# rf315i.net
KiCad netlist of a schematic drawn in EAGLE
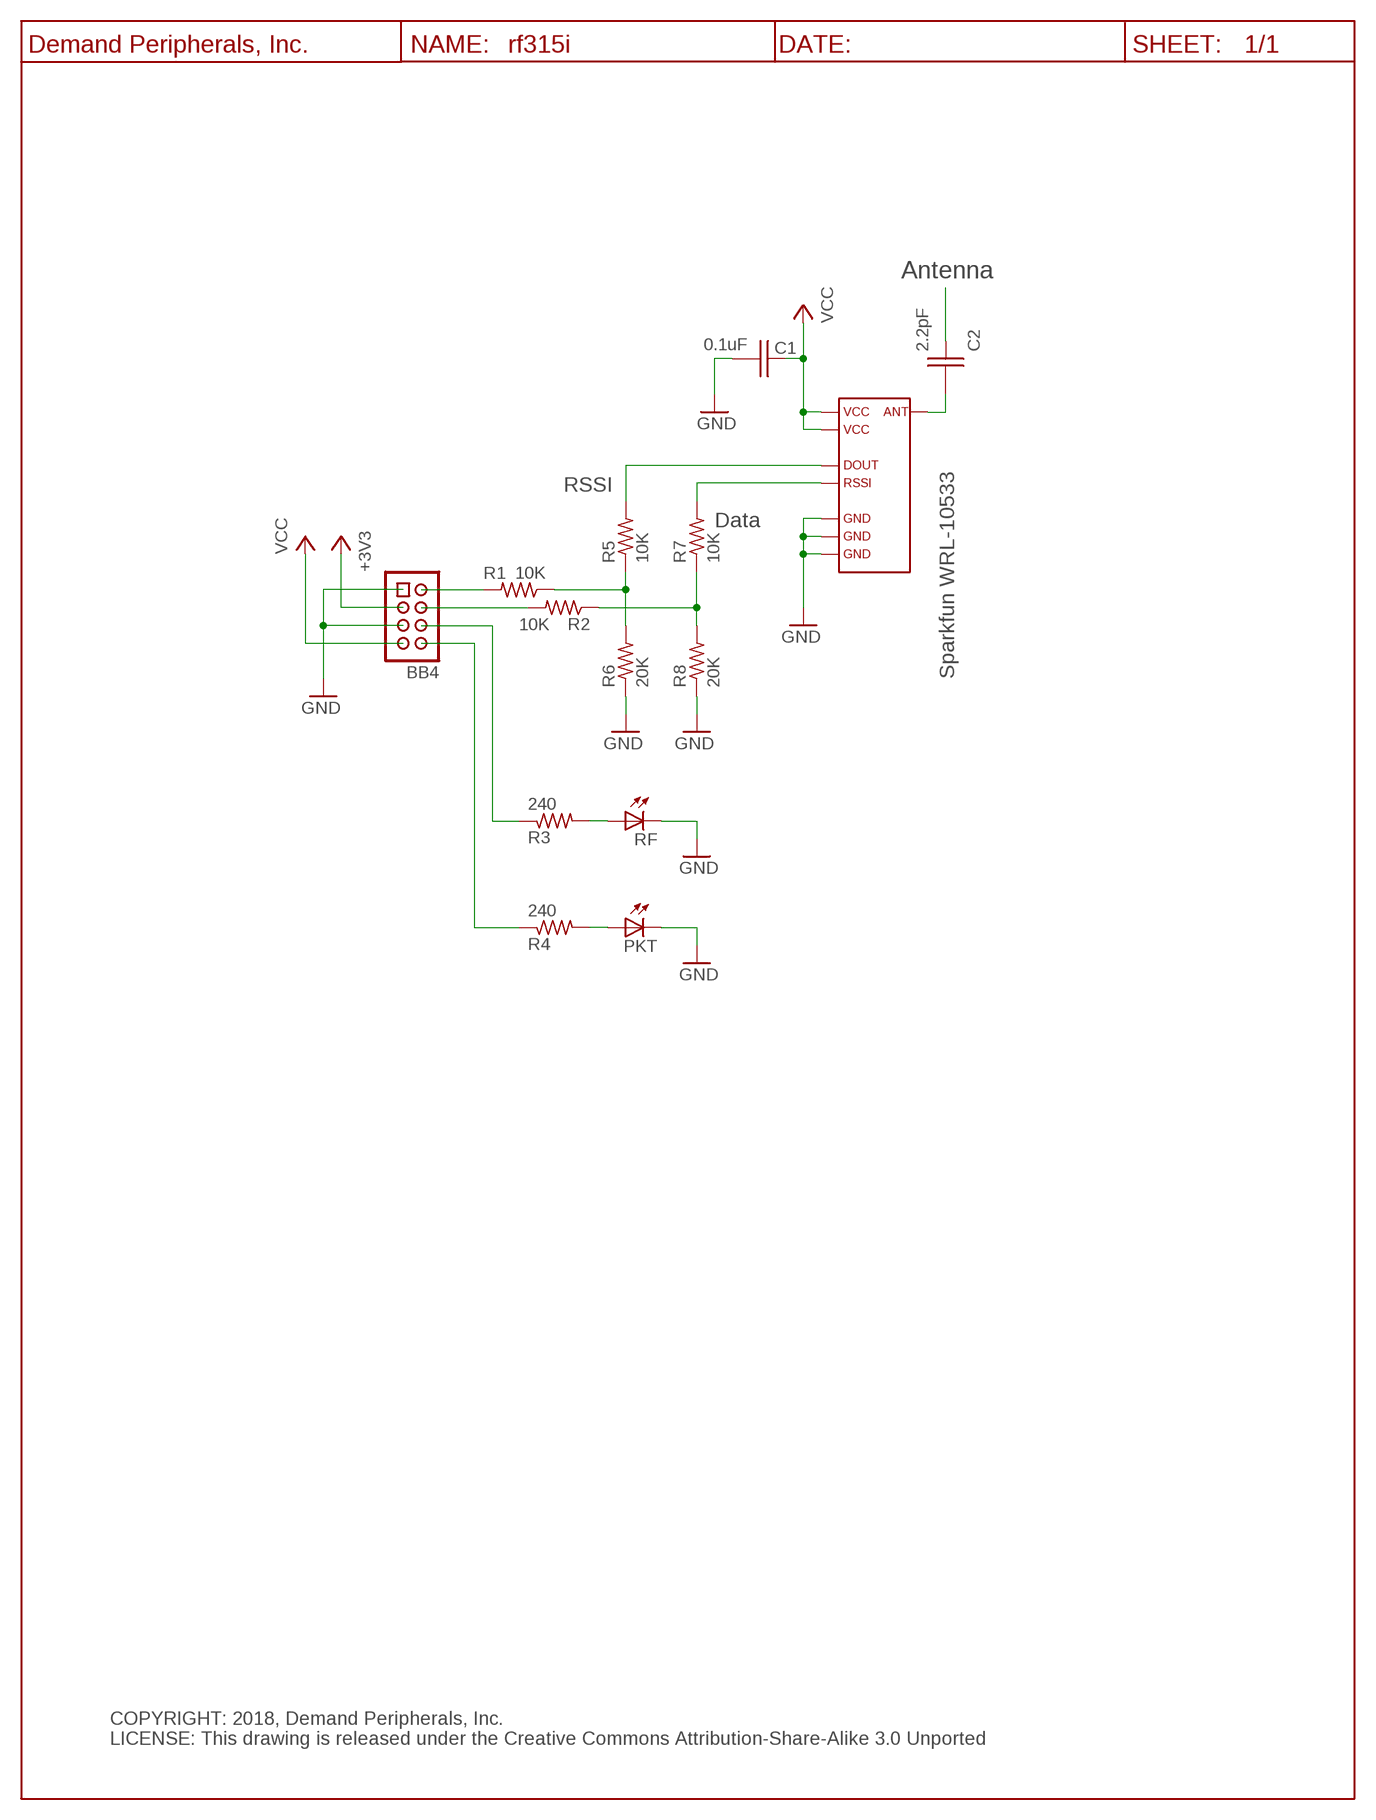
[diagram p0: schematic, sheet 1]

(export (version "E")
  (design (tool "Eeschema 10.0.6"))
  (components
    (comp (ref "BB4")
      (value "Keyed_Pin_Header_4x2(0.1\"x0.1\")")
      (footprint "eagle-import:HDR-4X2")
      (libsource (lib "eagle-import") (part "HDR-4X2-SHR"))
    )
    (comp (ref "C1")
      (value "0.1uF")
      (footprint "eagle-import:C0603")
      (libsource (lib "eagle-import") (part "C0.1UF_C0603"))
    )
    (comp (ref "C2")
      (value "2.2pF")
      (footprint "eagle-import:C0603")
      (libsource (lib "eagle-import") (part "C2.2PF_C0603"))
    )
    (comp (ref "PKT")
      (value "LED-0805-RED")
      (footprint "eagle-import:0805")
      (libsource (lib "eagle-import") (part "LED-0805-RED"))
    )
    (comp (ref "R1")
      (value "10K")
      (footprint "eagle-import:R0603")
      (libsource (lib "eagle-import") (part "R10K_R0603"))
    )
    (comp (ref "R2")
      (value "10K")
      (footprint "eagle-import:R0603")
      (libsource (lib "eagle-import") (part "R10K_R0603"))
    )
    (comp (ref "R3")
      (value "240")
      (footprint "eagle-import:R0603")
      (libsource (lib "eagle-import") (part "R240_"))
    )
    (comp (ref "R4")
      (value "240")
      (footprint "eagle-import:R0603")
      (libsource (lib "eagle-import") (part "R240_"))
    )
    (comp (ref "R5")
      (value "10K")
      (footprint "eagle-import:R0603")
      (libsource (lib "eagle-import") (part "R10K_R0603"))
    )
    (comp (ref "R6")
      (value "20K")
      (footprint "eagle-import:R0603")
      (libsource (lib "eagle-import") (part "R20K_R0603"))
    )
    (comp (ref "R7")
      (value "10K")
      (footprint "eagle-import:R0603")
      (libsource (lib "eagle-import") (part "R10K_R0603"))
    )
    (comp (ref "R8")
      (value "20K")
      (footprint "eagle-import:R0603")
      (libsource (lib "eagle-import") (part "R20K_R0603"))
    )
    (comp (ref "RF")
      (value "LED-0805-GRN")
      (footprint "eagle-import:0805")
      (libsource (lib "eagle-import") (part "LED-0805-GRN"))
    )
    (comp (ref "RF1")
      (value "WRL-10533")
      (footprint "eagle-import:RFLINK")
      (libsource (lib "eagle-import") (part "RFLINK"))
    )
    (comp (ref "U$1")
      (value "DP_FRAME_P")
      (footprint "eagle-import:P_FRAME")
      (libsource (lib "eagle-import") (part "DP_FRAME_P"))
    )
  )
  (nets
    (net (code "1") (name "+3V3") (class "Default")
      (node (ref "BB4") (pin "3") (pinfunction "3_3") (pintype "passive"))
    )
    (net (code "2") (name "GND") (class "Default")
      (node (ref "BB4") (pin "1") (pinfunction "1_1") (pintype "passive"))
      (node (ref "BB4") (pin "5") (pinfunction "5_5") (pintype "passive"))
      (node (ref "C1") (pin "2") (pinfunction "2_2") (pintype "passive"))
      (node (ref "PKT") (pin "C") (pinfunction "C_C") (pintype "passive"))
      (node (ref "R6") (pin "1") (pinfunction "1_1") (pintype "passive"))
      (node (ref "R8") (pin "1") (pinfunction "1_1") (pintype "passive"))
      (node (ref "RF") (pin "C") (pinfunction "C_C") (pintype "passive"))
      (node (ref "RF1") (pin "1") (pinfunction "GND1_1") (pintype "open_collector"))
      (node (ref "RF1") (pin "6") (pinfunction "GND3_6") (pintype "open_collector"))
      (node (ref "RF1") (pin "7") (pinfunction "GND2_7") (pintype "open_collector"))
    )
    (net (code "3") (name "Net-(BB4-Pad2)") (class "Default")
      (node (ref "BB4") (pin "2") (pinfunction "2_2") (pintype "passive"))
      (node (ref "R1") (pin "2") (pinfunction "2_2") (pintype "passive"))
    )
    (net (code "4") (name "Net-(BB4-Pad4)") (class "Default")
      (node (ref "BB4") (pin "4") (pinfunction "4_4") (pintype "passive"))
      (node (ref "R2") (pin "2") (pinfunction "2_2") (pintype "passive"))
    )
    (net (code "5") (name "Net-(BB4-Pad6)") (class "Default")
      (node (ref "BB4") (pin "6") (pinfunction "6_6") (pintype "passive"))
      (node (ref "R3") (pin "1") (pinfunction "1_1") (pintype "passive"))
    )
    (net (code "6") (name "Net-(BB4-Pad8)") (class "Default")
      (node (ref "BB4") (pin "8") (pinfunction "8_8") (pintype "passive"))
      (node (ref "R4") (pin "1") (pinfunction "1_1") (pintype "passive"))
    )
    (net (code "7") (name "Net-(PKT-PadA)") (class "Default")
      (node (ref "PKT") (pin "A") (pinfunction "A_A") (pintype "passive"))
      (node (ref "R4") (pin "2") (pinfunction "2_2") (pintype "passive"))
    )
    (net (code "8") (name "Net-(R1-Pad1)") (class "Default")
      (node (ref "R1") (pin "1") (pinfunction "1_1") (pintype "passive"))
      (node (ref "R5") (pin "1") (pinfunction "1_1") (pintype "passive"))
      (node (ref "R6") (pin "2") (pinfunction "2_2") (pintype "passive"))
    )
    (net (code "9") (name "Net-(R2-Pad1)") (class "Default")
      (node (ref "R2") (pin "1") (pinfunction "1_1") (pintype "passive"))
      (node (ref "R7") (pin "1") (pinfunction "1_1") (pintype "passive"))
      (node (ref "R8") (pin "2") (pinfunction "2_2") (pintype "passive"))
    )
    (net (code "10") (name "Net-(R3-Pad2)") (class "Default")
      (node (ref "R3") (pin "2") (pinfunction "2_2") (pintype "passive"))
      (node (ref "RF") (pin "A") (pinfunction "A_A") (pintype "passive"))
    )
    (net (code "11") (name "Net-(RF1-ANT)") (class "Default")
      (node (ref "C2") (pin "2") (pinfunction "2_2") (pintype "passive"))
      (node (ref "RF1") (pin "8") (pinfunction "ANT_8") (pintype "open_collector"))
    )
    (net (code "12") (name "Net-(RF1-DOUT)") (class "Default")
      (node (ref "R5") (pin "2") (pinfunction "2_2") (pintype "passive"))
      (node (ref "RF1") (pin "2") (pinfunction "DOUT_2") (pintype "open_collector"))
    )
    (net (code "13") (name "Net-(RF1-RSSI)") (class "Default")
      (node (ref "R7") (pin "2") (pinfunction "2_2") (pintype "passive"))
      (node (ref "RF1") (pin "3") (pinfunction "RSSI_3") (pintype "open_collector"))
    )
    (net (code "14") (name "VCC") (class "Default")
      (node (ref "BB4") (pin "7") (pinfunction "7_7") (pintype "passive"))
      (node (ref "C1") (pin "1") (pinfunction "1_1") (pintype "passive"))
      (node (ref "RF1") (pin "4") (pinfunction "VCC1_4") (pintype "open_collector"))
      (node (ref "RF1") (pin "5") (pinfunction "VCC2_5") (pintype "open_collector"))
    )
    (net (code "15") (name "unconnected-(C2-Pad1)") (class "Default")
      (node (ref "C2") (pin "1") (pinfunction "1_1") (pintype "passive"))
    )
  )
)
